# AK4637EN.net
KiCad netlist of a schematic drawn in Altium Designer
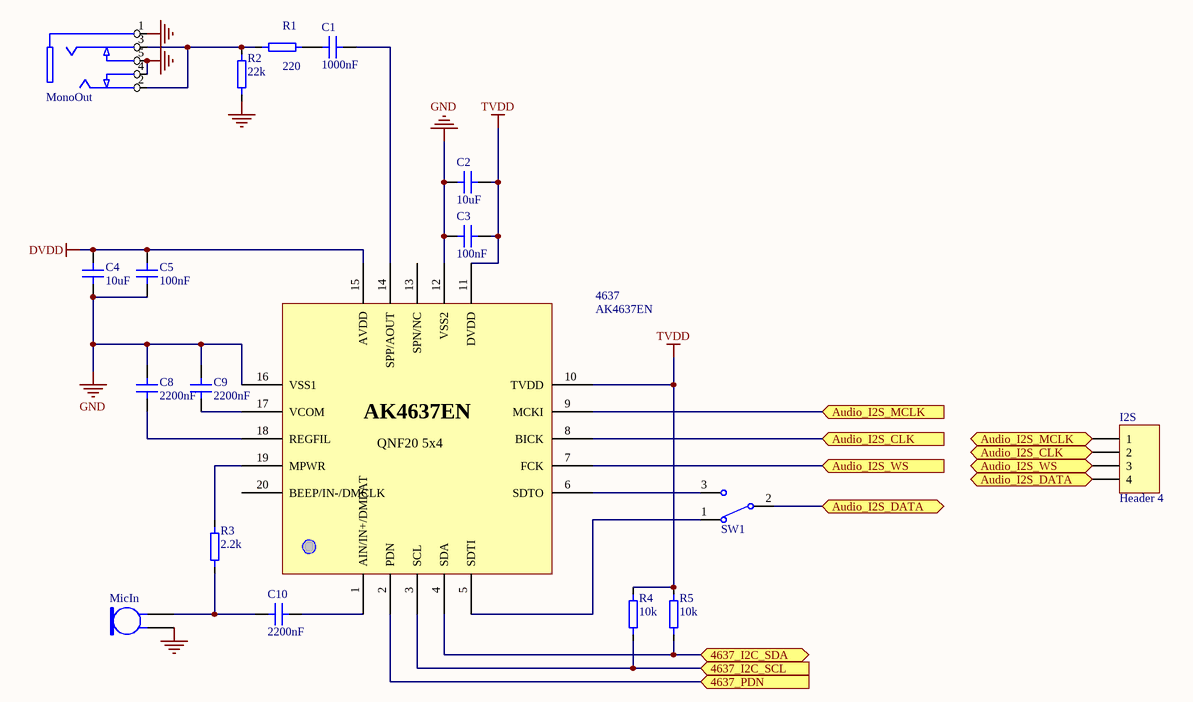
[diagram p0: AK4637EN.SchDoc]

(export (version "E")
  (design (tool "Eeschema 10.0.6"))
  (components
    (comp (ref "4637")
      (value "AK4637EN")
      (footprint "AK4637EN")
      (libsource (lib "WPU1611") (part "AK4637EN"))
    )
    (comp (ref "C1")
      (value "1000nF")
      (footprint "SMD 0603")
      (fields (field (name "Comment") "Cap SMD"))
      (libsource (lib "WPU1611") (part "Capicity SMD"))
    )
    (comp (ref "C2")
      (value "10uF")
      (footprint "SMD 0805")
      (fields (field (name "Comment") "Cap SMD"))
      (libsource (lib "WPU1611") (part "Capicity SMD"))
    )
    (comp (ref "C3")
      (value "100nF")
      (footprint "SMD 0603")
      (fields (field (name "Comment") "Cap SMD"))
      (libsource (lib "WPU1611") (part "Capicity SMD"))
    )
    (comp (ref "C4")
      (value "10uF")
      (footprint "SMD 0805")
      (fields (field (name "Comment") "Cap SMD"))
      (libsource (lib "WPU1611") (part "Capicity SMD"))
    )
    (comp (ref "C5")
      (value "100nF")
      (footprint "SMD 0603")
      (fields (field (name "Comment") "Cap SMD"))
      (libsource (lib "WPU1611") (part "Capicity SMD"))
    )
    (comp (ref "C8")
      (value "2200nF")
      (footprint "SMD 0603")
      (fields (field (name "Comment") "Cap SMD"))
      (libsource (lib "WPU1611") (part "Capicity SMD"))
    )
    (comp (ref "C9")
      (value "2200nF")
      (footprint "SMD 0603")
      (fields (field (name "Comment") "Cap SMD"))
      (libsource (lib "WPU1611") (part "Capicity SMD"))
    )
    (comp (ref "C10")
      (value "2200nF")
      (footprint "SMD 0603")
      (fields (field (name "Comment") "Cap SMD"))
      (libsource (lib "WPU1611") (part "Capicity SMD"))
    )
    (comp (ref "I2S")
      (value "Header 4")
      (footprint "HDR1X4")
      (description "Header, 4-Pin")
      (fields (field (name "PUBLISHER") "Altium Limited"))
      (libsource (lib "Miscellaneous Connectors") (part "Header 4"))
    )
    (comp (ref "MicIn")
      (value "Mic2")
      (footprint "PIN2")
      (description "Microphone")
      (fields (field (name "PUBLISHER") "Altium Limited"))
      (libsource (lib "Miscellaneous Devices") (part "Mic2"))
    )
    (comp (ref "MonoOut")
      (value "Audio Jack PJ-328")
      (footprint "Audio Jack PJ-328")
      (libsource (lib "WPU1611") (part "Audio Jack PJ-328"))
    )
    (comp (ref "R1")
      (value "220")
      (footprint "SMD 0603")
      (fields (field (name "Comment") "RES SMD"))
      (libsource (lib "WPU1611") (part "Resistor SMD"))
    )
    (comp (ref "R2")
      (value "22k")
      (footprint "SMD 0603")
      (fields (field (name "Comment") "RES SMD"))
      (libsource (lib "WPU1611") (part "Resistor SMD"))
    )
    (comp (ref "R3")
      (value "2.2k")
      (footprint "SMD 0603")
      (fields (field (name "Comment") "RES SMD"))
      (libsource (lib "WPU1611") (part "Resistor SMD"))
    )
    (comp (ref "R4")
      (value "10k")
      (footprint "SMD 0603")
      (fields (field (name "Comment") "RES SMD"))
      (libsource (lib "WPU1611") (part "Resistor SMD"))
    )
    (comp (ref "R5")
      (value "10k")
      (footprint "SMD 0603")
      (fields (field (name "Comment") "RES SMD"))
      (libsource (lib "WPU1611") (part "Resistor SMD"))
    )
    (comp (ref "SW1")
      (value "Switch_1")
      (footprint "Switch 2P2T")
      (libsource (lib "WPU1611") (part "Switch_1"))
    )
  )
  (nets
    (net (code "1") (name "/4637_I2C_SCL") (class "Default")
      (node (ref "4637") (pin "3") (pinfunction "SCL_3") (pintype "passive"))
      (node (ref "R4") (pin "1") (pintype "passive"))
    )
    (net (code "2") (name "/4637_I2C_SDA") (class "Default")
      (node (ref "4637") (pin "4") (pinfunction "SDA_4") (pintype "passive"))
      (node (ref "R5") (pin "1") (pintype "passive"))
    )
    (net (code "3") (name "/4637_PDN") (class "Default")
      (node (ref "4637") (pin "2") (pinfunction "PDN_2") (pintype "passive"))
    )
    (net (code "4") (name "/Audio_I2S_CLK") (class "Default")
      (node (ref "4637") (pin "8") (pinfunction "BICK_8") (pintype "passive"))
      (node (ref "I2S") (pin "2") (pinfunction "2_2") (pintype "passive"))
    )
    (net (code "5") (name "/Audio_I2S_DATA") (class "Default")
      (node (ref "I2S") (pin "4") (pinfunction "4_4") (pintype "passive"))
      (node (ref "SW1") (pin "2") (pintype "passive"))
    )
    (net (code "6") (name "/Audio_I2S_MCLK") (class "Default")
      (node (ref "4637") (pin "9") (pinfunction "MCKI_9") (pintype "passive"))
      (node (ref "I2S") (pin "1") (pinfunction "1_1") (pintype "passive"))
    )
    (net (code "7") (name "/Audio_I2S_WS") (class "Default")
      (node (ref "4637") (pin "7") (pinfunction "FCK_7") (pintype "passive"))
      (node (ref "I2S") (pin "3") (pinfunction "3_3") (pintype "passive"))
    )
    (net (code "8") (name "DVDD") (class "Default")
      (node (ref "4637") (pin "15") (pinfunction "AVDD_15") (pintype "passive"))
      (node (ref "C4") (pin "2") (pintype "passive"))
      (node (ref "C5") (pin "2") (pintype "passive"))
    )
    (net (code "9") (name "GND") (class "Default")
      (node (ref "4637") (pin "12") (pinfunction "VSS2_12") (pintype "passive"))
      (node (ref "4637") (pin "16") (pinfunction "VSS1_16") (pintype "passive"))
      (node (ref "C2") (pin "1") (pintype "passive"))
      (node (ref "C3") (pin "1") (pintype "passive"))
      (node (ref "C4") (pin "1") (pintype "passive"))
      (node (ref "C5") (pin "1") (pintype "passive"))
      (node (ref "C8") (pin "2") (pintype "passive"))
      (node (ref "C9") (pin "2") (pintype "passive"))
      (node (ref "MicIn") (pin "1") (pinfunction "1_1") (pintype "passive"))
      (node (ref "MonoOut") (pin "1") (pinfunction "GND_1") (pintype "passive"))
      (node (ref "MonoOut") (pin "4") (pinfunction "RIGHT_SW_4") (pintype "passive"))
      (node (ref "MonoOut") (pin "5") (pinfunction "LEFT_SW_5") (pintype "passive"))
      (node (ref "R2") (pin "1") (pintype "passive"))
    )
    (net (code "10") (name "Net-(4637-AIN{slash}IN+{slash}DMDAT)") (class "Default")
      (node (ref "4637") (pin "1") (pinfunction "AIN/IN+/DMDAT_1") (pintype "passive"))
      (node (ref "C10") (pin "2") (pintype "passive"))
    )
    (net (code "11") (name "Net-(4637-MPWR)") (class "Default")
      (node (ref "4637") (pin "19") (pinfunction "MPWR_19") (pintype "passive"))
      (node (ref "R3") (pin "2") (pintype "passive"))
    )
    (net (code "12") (name "Net-(4637-REGFIL)") (class "Default")
      (node (ref "4637") (pin "18") (pinfunction "REGFIL_18") (pintype "passive"))
      (node (ref "C8") (pin "1") (pintype "passive"))
    )
    (net (code "13") (name "Net-(4637-SDTI)") (class "Default")
      (node (ref "4637") (pin "5") (pinfunction "SDTI_5") (pintype "passive"))
      (node (ref "SW1") (pin "1") (pintype "passive"))
    )
    (net (code "14") (name "Net-(4637-SDTO)") (class "Default")
      (node (ref "4637") (pin "6") (pinfunction "SDTO_6") (pintype "passive"))
      (node (ref "SW1") (pin "3") (pintype "passive"))
    )
    (net (code "15") (name "Net-(4637-SPP{slash}AOUT)") (class "Default")
      (node (ref "4637") (pin "14") (pinfunction "SPP/AOUT_14") (pintype "passive"))
      (node (ref "C1") (pin "2") (pintype "passive"))
    )
    (net (code "16") (name "Net-(4637-VCOM)") (class "Default")
      (node (ref "4637") (pin "17") (pinfunction "VCOM_17") (pintype "passive"))
      (node (ref "C9") (pin "1") (pintype "passive"))
    )
    (net (code "17") (name "Net-(C1-Pad1)") (class "Default")
      (node (ref "C1") (pin "1") (pintype "passive"))
      (node (ref "R1") (pin "2") (pintype "passive"))
    )
    (net (code "18") (name "Net-(C10-Pad1)") (class "Default")
      (node (ref "C10") (pin "1") (pintype "passive"))
      (node (ref "MicIn") (pin "2") (pinfunction "2_2") (pintype "passive"))
      (node (ref "R3") (pin "1") (pintype "passive"))
    )
    (net (code "19") (name "Net-(MonoOut-LEFT)") (class "Default")
      (node (ref "MonoOut") (pin "2") (pinfunction "RIGHT_2") (pintype "passive"))
      (node (ref "MonoOut") (pin "3") (pinfunction "LEFT_3") (pintype "passive"))
      (node (ref "R1") (pin "1") (pintype "passive"))
      (node (ref "R2") (pin "2") (pintype "passive"))
    )
    (net (code "20") (name "TVDD") (class "Default")
      (node (ref "4637") (pin "10") (pinfunction "TVDD_10") (pintype "passive"))
      (node (ref "4637") (pin "11") (pinfunction "DVDD_11") (pintype "passive"))
      (node (ref "C2") (pin "2") (pintype "passive"))
      (node (ref "C3") (pin "2") (pintype "passive"))
      (node (ref "R4") (pin "2") (pintype "passive"))
      (node (ref "R5") (pin "2") (pintype "passive"))
    )
    (net (code "21") (name "unconnected-(4637-BEEP{slash}IN-{slash}DMCLK-Pad20)") (class "Default")
      (node (ref "4637") (pin "20") (pinfunction "BEEP/IN-/DMCLK_20") (pintype "passive"))
    )
    (net (code "22") (name "unconnected-(4637-SPN{slash}NC-Pad13)") (class "Default")
      (node (ref "4637") (pin "13") (pinfunction "SPN/NC_13") (pintype "passive"))
    )
  )
)
